# STRWL-S05-V00-Master-PSU3V3-300mA.net
KiCad netlist of a schematic drawn in Altium Designer
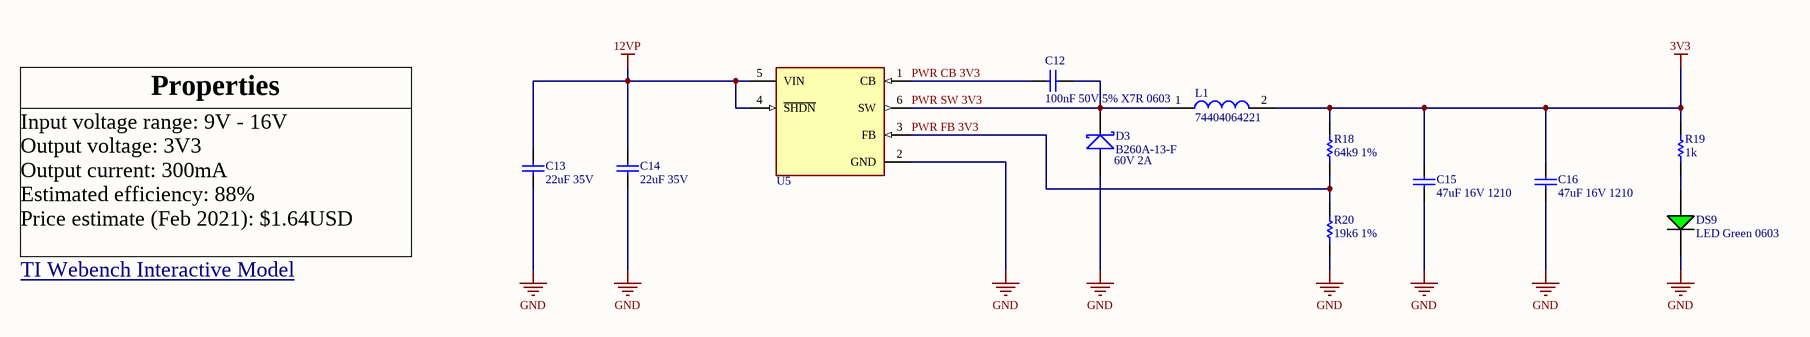
[diagram p0: STRWL-S05-V00-Master-PSU3V3-300mA.SchDoc]

(export (version "E")
  (design (tool "Eeschema 10.0.6"))
  (components
    (comp (ref "C12")
      (value "100nF 50V 5% X7R 0603")
      (footprint "Cap_Ceramic_0603")
      (description "Capacitor, Ceramic, SMD, 100nF, 50V, 5%, X7R, 0603")
      (libsource (lib "StandardCapacitors") (part "100nF 50V 5% X7R 0603"))
    )
    (comp (ref "C13")
      (value "22uF 35V")
      (footprint "Cap_Ceramic_1206")
      (description "22µF ±20% 35V Ceramic Capacitor X5R 1206 (3216 Metric)")
      (libsource (lib "StandardCapacitors") (part "22uF 35V 20% X5R 1206"))
    )
    (comp (ref "C14")
      (value "22uF 35V")
      (footprint "Cap_Ceramic_1206")
      (description "22µF ±20% 35V Ceramic Capacitor X5R 1206 (3216 Metric)")
      (libsource (lib "StandardCapacitors") (part "22uF 35V 20% X5R 1206"))
    )
    (comp (ref "C15")
      (value "47uF 16V 1210")
      (footprint "Cap_Ceramic_1210")
      (description "Capacitor, Ceramic, SMD, 47uF, 16V, 5%, X7R, 1210")
      (libsource (lib "StandardCapacitors") (part "47uF 16V 10% X7R 1210"))
    )
    (comp (ref "C16")
      (value "47uF 16V 1210")
      (footprint "Cap_Ceramic_1210")
      (description "Capacitor, Ceramic, SMD, 47uF, 16V, 5%, X7R, 1210")
      (libsource (lib "StandardCapacitors") (part "47uF 16V 10% X7R 1210"))
    )
    (comp (ref "D3")
      (value "B260A-13-F")
      (footprint "SMA")
      (description "Diode, Schottky Barrier Rectifier, 60 V, 2 A, B260A-13-F")
      (libsource (lib "QUTMS_DiodeLibrary") (part "B260A-13-F"))
    )
    (comp (ref "DS9")
      (value "LED Green 0603")
      (footprint "LED GREEN 0603")
      (libsource (lib "QUTMS_LEDLibrary") (part "LED Green 0603"))
    )
    (comp (ref "L1")
      (value "74404064221")
      (footprint "Inductor_6x6mm")
      (description "FIXED IND 220UH 660MA 850 MOHM")
      (libsource (lib "QUTMS-MCISOLibrary") (part "74404064221"))
    )
    (comp (ref "R18")
      (value "64k9 1%")
      (footprint "Res_ThinFilm_0603")
      (description "Resistor, SMD, 64k9, 0.1W, 5%, 0603")
      (libsource (lib "StandardResistors") (part "64k9 1% 0603"))
    )
    (comp (ref "R19")
      (value "1k")
      (footprint "Res_ThinFilm_0603")
      (description "Resistor, SMD, 1k, 0.1W, 5%, 0603")
      (libsource (lib "StandardResistors") (part "1k 5% 0603"))
    )
    (comp (ref "R20")
      (value "19k6 1%")
      (footprint "Res_ThinFilm_0603")
      (description "Resistor, SMD, 19k6, 0.1W, 5%, 0603")
      (libsource (lib "StandardResistors") (part "19k6 1% 0603"))
    )
    (comp (ref "U5")
      (value "LMR14010ADDCR")
      (footprint "Texas_Instruments_DDC0006A_IPC_A")
      (libsource (lib "IC_Texas_Instruments_LMR14010ADDCR_eec") (part "LMR14010ADDCR"))
    )
  )
  (nets
    (net (code "1") (name "/PWR CB 3V3") (class "Default")
      (node (ref "C12") (pin "1") (pinfunction "1_1") (pintype "passive"))
      (node (ref "U5") (pin "1") (pinfunction "CB_1") (pintype "input"))
    )
    (net (code "2") (name "/PWR FB 3V3") (class "Default")
      (node (ref "R18") (pin "1") (pinfunction "1_1") (pintype "passive"))
      (node (ref "R20") (pin "2") (pinfunction "2_2") (pintype "passive"))
      (node (ref "U5") (pin "3") (pinfunction "FB_3") (pintype "input"))
    )
    (net (code "3") (name "/PWR SW 3V3") (class "Default")
      (node (ref "C12") (pin "2") (pinfunction "2_2") (pintype "passive"))
      (node (ref "D3") (pin "K") (pinfunction "K_K") (pintype "passive"))
      (node (ref "L1") (pin "1") (pinfunction "1_1") (pintype "passive"))
      (node (ref "U5") (pin "6") (pinfunction "SW_6") (pintype "output"))
    )
    (net (code "4") (name "3V3") (class "Default")
      (node (ref "C15") (pin "2") (pinfunction "2_2") (pintype "passive"))
      (node (ref "C16") (pin "2") (pinfunction "2_2") (pintype "passive"))
      (node (ref "L1") (pin "2") (pinfunction "2_2") (pintype "passive"))
      (node (ref "R18") (pin "2") (pinfunction "2_2") (pintype "passive"))
      (node (ref "R19") (pin "2") (pinfunction "2_2") (pintype "passive"))
    )
    (net (code "5") (name "12VP") (class "Default")
      (node (ref "C13") (pin "1") (pinfunction "1_1") (pintype "passive"))
      (node (ref "C14") (pin "1") (pinfunction "1_1") (pintype "passive"))
      (node (ref "U5") (pin "4") (pinfunction "~{SHDN}_4") (pintype "input"))
      (node (ref "U5") (pin "5") (pinfunction "VIN_5") (pintype "power_in"))
    )
    (net (code "6") (name "GND") (class "Default")
      (node (ref "C13") (pin "2") (pinfunction "2_2") (pintype "passive"))
      (node (ref "C14") (pin "2") (pinfunction "2_2") (pintype "passive"))
      (node (ref "C15") (pin "1") (pinfunction "1_1") (pintype "passive"))
      (node (ref "C16") (pin "1") (pinfunction "1_1") (pintype "passive"))
      (node (ref "D3") (pin "A") (pinfunction "A_A") (pintype "passive"))
      (node (ref "DS9") (pin "2") (pinfunction "C_2") (pintype "passive"))
      (node (ref "R20") (pin "1") (pinfunction "1_1") (pintype "passive"))
      (node (ref "U5") (pin "2") (pinfunction "GND_2") (pintype "power_in"))
    )
    (net (code "7") (name "Net-(DS9-A)") (class "Default")
      (node (ref "DS9") (pin "1") (pinfunction "A_1") (pintype "passive"))
      (node (ref "R19") (pin "1") (pinfunction "1_1") (pintype "passive"))
    )
  )
)
